# Dogfish3D_-_MCU_-_ATSAMD21G18_R1a.net
KiCad netlist of a schematic drawn in Altium Designer
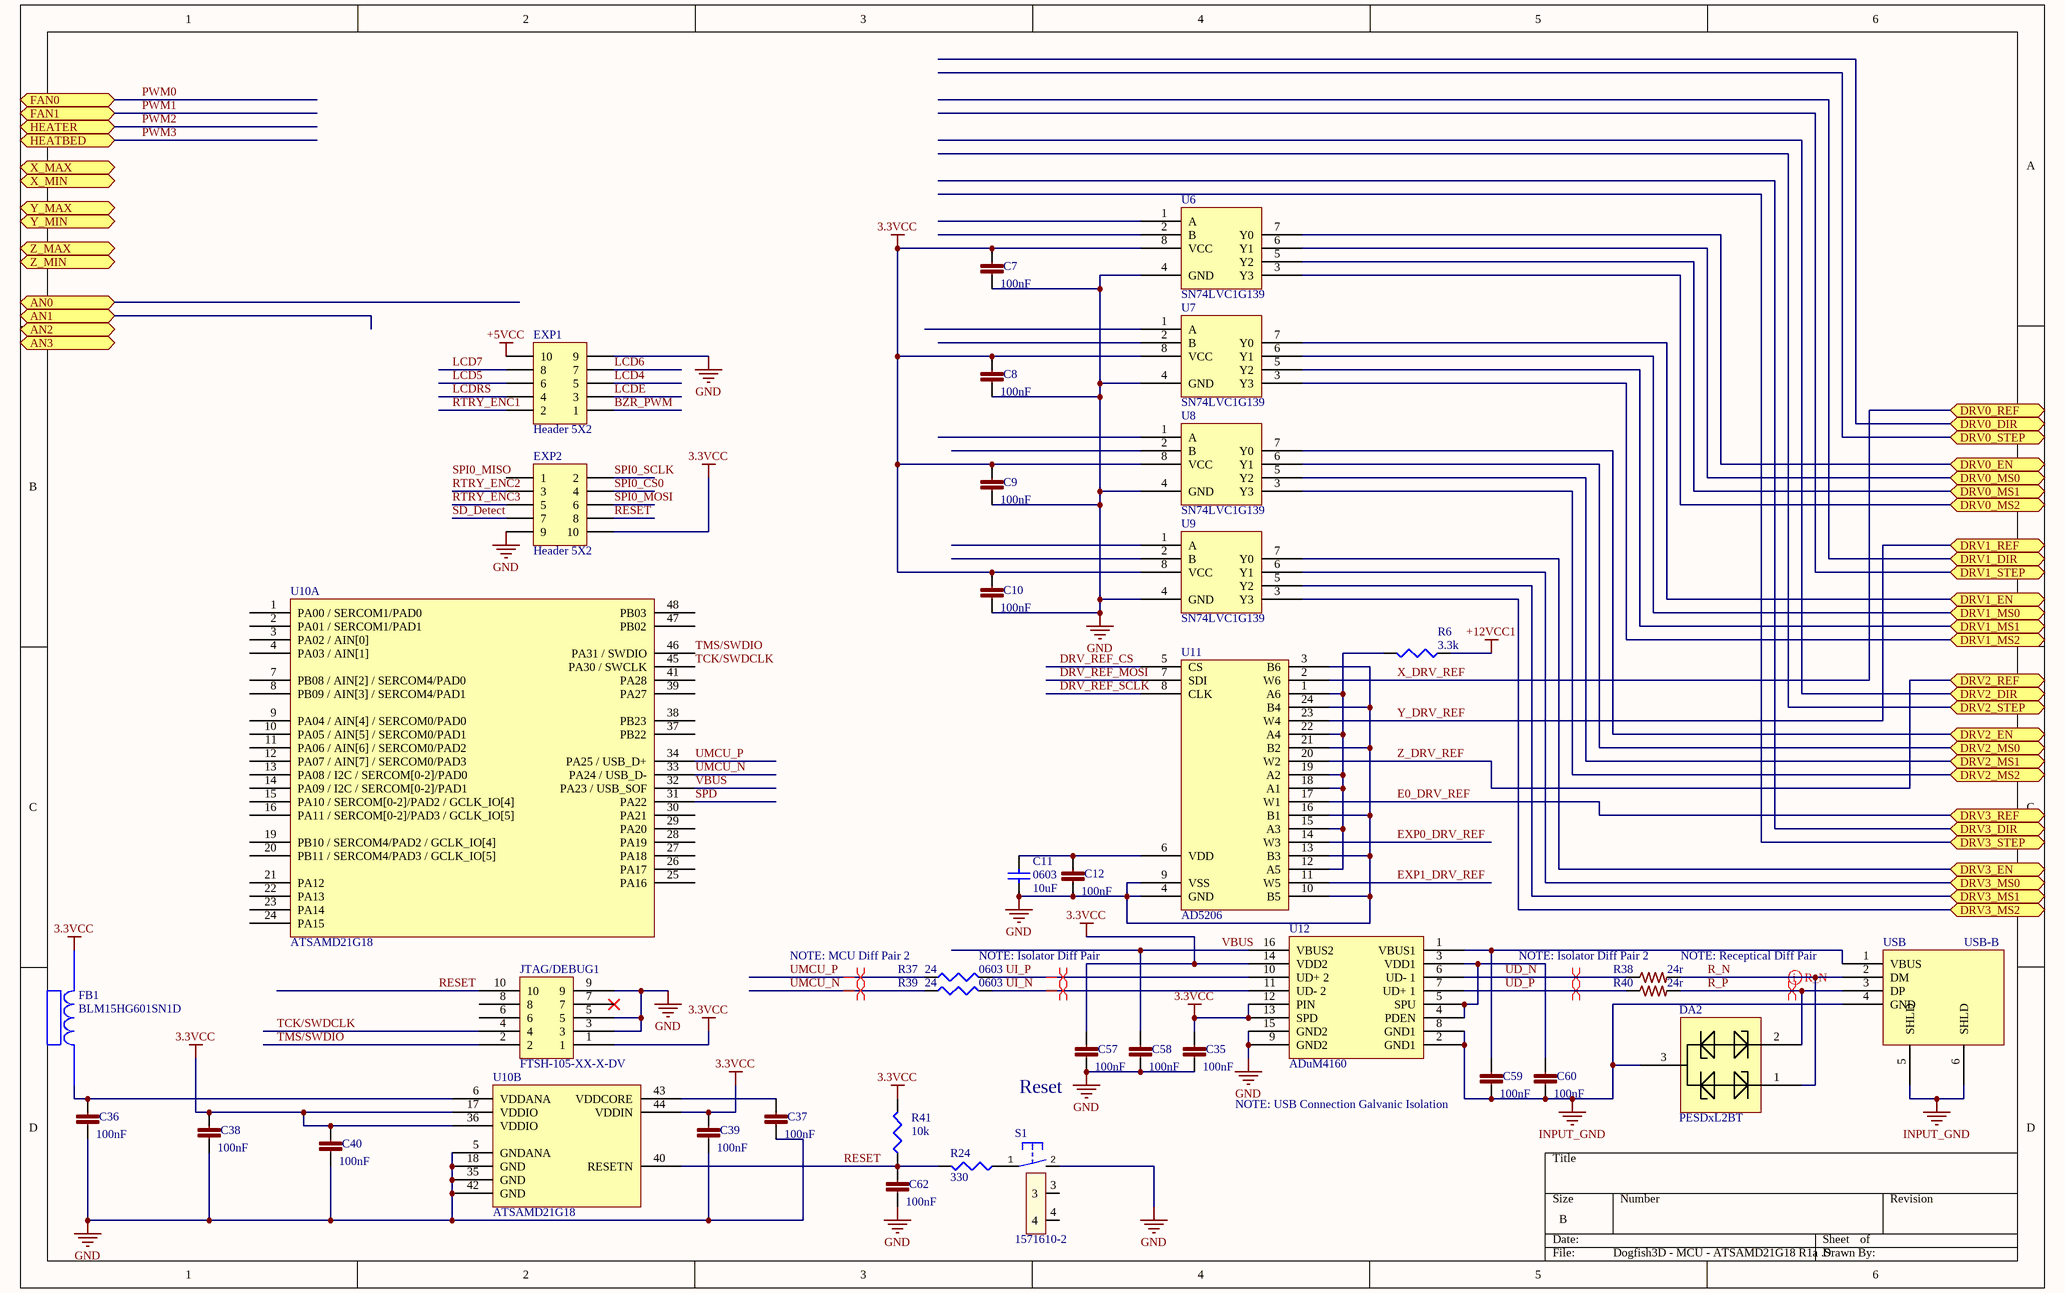
[diagram p0: Dogfish3D - MCU - ATSAMD21G18 R1a .SchDoc]

(export (version "E")
  (design (tool "Eeschema 10.0.6"))
  (components
    (comp (ref "C7")
      (value "100nF")
      (footprint "C0402")
      (description "CAP CER 0402 100nF 16V 10% X7R")
      (fields
        (field (name "MANUFACTURERPARTNUMBER") "GRM155R71C104KA88D")
        (field (name "PUBLISHER") "UltiMachine")
      )
      (libsource (lib "3Delight") (part "GRM155R71C104KA88D"))
    )
    (comp (ref "C8")
      (value "100nF")
      (footprint "C0402")
      (description "CAP CER 0402 100nF 16V 10% X7R")
      (fields
        (field (name "MANUFACTURERPARTNUMBER") "GRM155R71C104KA88D")
        (field (name "PUBLISHER") "UltiMachine")
      )
      (libsource (lib "3Delight") (part "GRM155R71C104KA88D"))
    )
    (comp (ref "C9")
      (value "100nF")
      (footprint "C0402")
      (description "CAP CER 0402 100nF 16V 10% X7R")
      (fields
        (field (name "MANUFACTURERPARTNUMBER") "GRM155R71C104KA88D")
        (field (name "PUBLISHER") "UltiMachine")
      )
      (libsource (lib "3Delight") (part "GRM155R71C104KA88D"))
    )
    (comp (ref "C10")
      (value "100nF")
      (footprint "C0402")
      (description "CAP CER 0402 100nF 16V 10% X7R")
      (fields
        (field (name "MANUFACTURERPARTNUMBER") "GRM155R71C104KA88D")
        (field (name "PUBLISHER") "UltiMachine")
      )
      (libsource (lib "3Delight") (part "GRM155R71C104KA88D"))
    )
    (comp (ref "C11")
      (value "0603")
      (footprint "1608[0603]")
      (description "Capacitor (Semiconductor SIM Model)")
      (fields (field (name "ALTIUM_VALUE") "10uF") (field (name "PUBLISHER") "Altium Limited"))
      (libsource (lib "Miscellaneous Devices") (part "Cap Semi"))
    )
    (comp (ref "C12")
      (value "100nF")
      (footprint "C0402")
      (description "CAP CER 0402 100nF 16V 10% X7R")
      (fields
        (field (name "MANUFACTURERPARTNUMBER") "GRM155R71C104KA88D")
        (field (name "PUBLISHER") "UltiMachine")
      )
      (libsource (lib "3Delight") (part "GRM155R71C104KA88D"))
    )
    (comp (ref "C35")
      (value "100nF")
      (footprint "C0402")
      (description "CAP CER 0402 100nF 16V 10% X7R")
      (fields
        (field (name "MANUFACTURERPARTNUMBER") "GRM155R71C104KA88D")
        (field (name "PUBLISHER") "UltiMachine")
      )
      (libsource (lib "3Delight") (part "GRM155R71C104KA88D"))
    )
    (comp (ref "C36")
      (value "100nF")
      (footprint "C0402")
      (description "CAP CER 0402 100nF 16V 10% X7R")
      (fields
        (field (name "MANUFACTURERPARTNUMBER") "GRM155R71C104KA88D")
        (field (name "PUBLISHER") "UltiMachine")
      )
      (libsource (lib "3Delight") (part "GRM155R71C104KA88D"))
    )
    (comp (ref "C37")
      (value "100nF")
      (footprint "C0402")
      (description "CAP CER 0402 100nF 16V 10% X7R")
      (fields
        (field (name "MANUFACTURERPARTNUMBER") "GRM155R71C104KA88D")
        (field (name "PUBLISHER") "UltiMachine")
      )
      (libsource (lib "3Delight") (part "GRM155R71C104KA88D"))
    )
    (comp (ref "C38")
      (value "100nF")
      (footprint "C0402")
      (description "CAP CER 0402 100nF 16V 10% X7R")
      (fields
        (field (name "MANUFACTURERPARTNUMBER") "GRM155R71C104KA88D")
        (field (name "PUBLISHER") "UltiMachine")
      )
      (libsource (lib "3Delight") (part "GRM155R71C104KA88D"))
    )
    (comp (ref "C39")
      (value "100nF")
      (footprint "C0402")
      (description "CAP CER 0402 100nF 16V 10% X7R")
      (fields
        (field (name "MANUFACTURERPARTNUMBER") "GRM155R71C104KA88D")
        (field (name "PUBLISHER") "UltiMachine")
      )
      (libsource (lib "3Delight") (part "GRM155R71C104KA88D"))
    )
    (comp (ref "C40")
      (value "100nF")
      (footprint "C0402")
      (description "CAP CER 0402 100nF 16V 10% X7R")
      (fields
        (field (name "MANUFACTURERPARTNUMBER") "GRM155R71C104KA88D")
        (field (name "PUBLISHER") "UltiMachine")
      )
      (libsource (lib "3Delight") (part "GRM155R71C104KA88D"))
    )
    (comp (ref "C57")
      (value "100nF")
      (footprint "C0402")
      (description "CAP CER 0402 100nF 16V 10% X7R")
      (fields
        (field (name "MANUFACTURERPARTNUMBER") "GRM155R71C104KA88D")
        (field (name "PUBLISHER") "UltiMachine")
      )
      (libsource (lib "3Delight") (part "GRM155R71C104KA88D"))
    )
    (comp (ref "C58")
      (value "100nF")
      (footprint "C0402")
      (description "CAP CER 0402 100nF 16V 10% X7R")
      (fields
        (field (name "MANUFACTURERPARTNUMBER") "GRM155R71C104KA88D")
        (field (name "PUBLISHER") "UltiMachine")
      )
      (libsource (lib "3Delight") (part "GRM155R71C104KA88D"))
    )
    (comp (ref "C59")
      (value "100nF")
      (footprint "C0402")
      (description "CAP CER 0402 100nF 16V 10% X7R")
      (fields
        (field (name "MANUFACTURERPARTNUMBER") "GRM155R71C104KA88D")
        (field (name "PUBLISHER") "UltiMachine")
      )
      (libsource (lib "3Delight") (part "GRM155R71C104KA88D"))
    )
    (comp (ref "C60")
      (value "100nF")
      (footprint "C0402")
      (description "CAP CER 0402 100nF 16V 10% X7R")
      (fields
        (field (name "MANUFACTURERPARTNUMBER") "GRM155R71C104KA88D")
        (field (name "PUBLISHER") "UltiMachine")
      )
      (libsource (lib "3Delight") (part "GRM155R71C104KA88D"))
    )
    (comp (ref "C62")
      (value "100nF")
      (footprint "C0402")
      (description "CAP CER 0402 100nF 16V 10% X7R")
      (fields
        (field (name "MANUFACTURERPARTNUMBER") "GRM155R71C104KA88D")
        (field (name "PUBLISHER") "UltiMachine")
      )
      (libsource (lib "3Delight") (part "GRM155R71C104KA88D"))
    )
    (comp (ref "DA2")
      (value "PESDxL2BT")
      (footprint "SOT95P230X110-3N")
      (description "PESDxL2BT TVS Diode Array 2x")
      (libsource (lib "ZMBo Schematic Library") (part "PESDxL2BT"))
    )
    (comp (ref "EXP1")
      (value "Header 5X2")
      (footprint "HDR2X5")
      (description "Header, 5-Pin, Dual row")
      (fields (field (name "PUBLISHER") "Altium Limited"))
      (libsource (lib "") (part "Header 5X2_1"))
    )
    (comp (ref "EXP2")
      (value "Header 5X2")
      (footprint "HDR2X5")
      (description "Header, 5-Pin, Dual row")
      (fields (field (name "PUBLISHER") "Altium Limited"))
      (libsource (lib "Miscellaneous Connectors") (part "Header 5X2"))
    )
    (comp (ref "FB1")
      (value "BLM15HG601SN1D")
      (footprint "BLM18PG121SN1D")
      (libsource (lib "AHD Part Library") (part "BLM15HG601SN1D"))
    )
    (comp (ref "JTAG/DEBUG1")
      (value "FTSH-105-XX-X-DV")
      (footprint "FTSH-105-XX-X-DV")
      (libsource (lib "Adams Altium Library") (part "ARM Cortex JTAG-DEBUG Header"))
    )
    (comp (ref "R6")
      (value "3.3k")
      (footprint "J1-0603")
      (description "Resistor")
      (fields (field (name "Comment") "Res3") (field (name "PUBLISHER") "Altium Limited"))
      (libsource (lib "Miscellaneous Devices") (part "Res3"))
    )
    (comp (ref "R24")
      (value "330")
      (footprint "J1-0603")
      (description "Resistor")
      (fields (field (name "Comment") "Res3") (field (name "PUBLISHER") "Altium Limited"))
      (libsource (lib "Miscellaneous Devices") (part "Res3"))
    )
    (comp (ref "R37")
      (value "0603")
      (footprint "J1-0603")
      (description "Resistor")
      (fields (field (name "ALTIUM_VALUE") "24") (field (name "PUBLISHER") "Altium Limited"))
      (libsource (lib "Miscellaneous Devices") (part "Res3"))
    )
    (comp (ref "R38")
      (value "24r")
      (footprint "R0603")
      (description "RES SMD 24 OHM 1% 1/10W 0603")
      (fields
        (field (name "MANUFACTURER") "Samsung")
        (field (name "MANUFACTURERPARTNUMBER") "RC0603FR-07100KL")
        (field (name "PUBLISHER") "UltiMachine")
      )
      (libsource (lib "Tigershark3D") (part "RC1608F240CS"))
    )
    (comp (ref "R39")
      (value "0603")
      (footprint "J1-0603")
      (description "Resistor")
      (fields (field (name "ALTIUM_VALUE") "24") (field (name "PUBLISHER") "Altium Limited"))
      (libsource (lib "Miscellaneous Devices") (part "Res3"))
    )
    (comp (ref "R40")
      (value "24r")
      (footprint "R0603")
      (description "RES SMD 24 OHM 1% 1/10W 0603")
      (fields
        (field (name "MANUFACTURER") "Samsung")
        (field (name "MANUFACTURERPARTNUMBER") "RC0603FR-07100KL")
        (field (name "PUBLISHER") "UltiMachine")
      )
      (libsource (lib "Tigershark3D") (part "RC1608F240CS"))
    )
    (comp (ref "R41")
      (value "10k")
      (footprint "J1-0603")
      (description "Resistor")
      (fields (field (name "Comment") "Res3") (field (name "PUBLISHER") "Altium Limited"))
      (libsource (lib "Miscellaneous Devices") (part "Res3"))
    )
    (comp (ref "S1")
      (value "1571610-2")
      (footprint "B3F-31XX")
      (description "SWTCH Momentary Washable")
      (fields
        (field (name "MANUFACTURER") "Omron")
        (field (name "MANUFACTURER_1") "TE")
        (field (name "PUBLISHER") "UltiMachine")
      )
      (libsource (lib "ZMBo Schematic Library") (part "1571610-2_1"))
    )
    (comp (ref "U6")
      (value "SN74LVC1G139")
      (footprint "Ti DCU (R-PDSO-G8) SOIC - SN74VC1G139")
      (libsource (lib "Dogfish3D") (part "SN74LVC1G139"))
    )
    (comp (ref "U7")
      (value "SN74LVC1G139")
      (footprint "Ti DCU (R-PDSO-G8) SOIC - SN74VC1G139")
      (libsource (lib "Dogfish3D") (part "SN74LVC1G139"))
    )
    (comp (ref "U8")
      (value "SN74LVC1G139")
      (footprint "Ti DCU (R-PDSO-G8) SOIC - SN74VC1G139")
      (libsource (lib "Dogfish3D") (part "SN74LVC1G139"))
    )
    (comp (ref "U9")
      (value "SN74LVC1G139")
      (footprint "Ti DCU (R-PDSO-G8) SOIC - SN74VC1G139")
      (libsource (lib "Dogfish3D") (part "SN74LVC1G139"))
    )
    (comp (ref "U10")
      (value "ATSAMD21G18")
      (footprint "TSQFP50P900X900X120-48N")
      (libsource (lib "Dogfish3D") (part "ATSAMD21G18"))
    )
    (comp (ref "U11")
      (value "AD5206")
      (footprint "AD5206 & AD5204")
      (libsource (lib "ZMBo Schematic Library") (part "AD5206"))
    )
    (comp (ref "U12")
      (value "ADuM4160")
      (footprint "ADuM4160")
      (description "USB Opto Isolator")
      (libsource (lib "ZMBo Schematic Library") (part "ADuM4160"))
    )
    (comp (ref "USB")
      (value "USB-B")
      (footprint "PN61729")
      (libsource (lib "ZMBo Schematic Library") (part "USB-B"))
    )
  )
  (nets
    (net (code "1") (name "+5VCC") (class "Default")
      (node (ref "EXP1") (pin "10") (pinfunction "10_10") (pintype "passive"))
    )
    (net (code "2") (name "+12VCC1") (class "Default")
      (node (ref "R6") (pin "1") (pinfunction "1_1") (pintype "passive"))
    )
    (net (code "7") (name "/BZR_PWM") (class "Default")
      (node (ref "EXP1") (pin "1") (pinfunction "1_1") (pintype "passive"))
    )
    (net (code "9") (name "/DRV0_EN") (class "Default")
      (node (ref "U6") (pin "7") (pinfunction "Y0_7") (pintype "passive"))
    )
    (net (code "10") (name "/DRV0_MS0") (class "Default")
      (node (ref "U6") (pin "6") (pinfunction "Y1_6") (pintype "passive"))
    )
    (net (code "11") (name "/DRV0_MS1") (class "Default")
      (node (ref "U6") (pin "5") (pinfunction "Y2_5") (pintype "passive"))
    )
    (net (code "12") (name "/DRV0_MS2") (class "Default")
      (node (ref "U6") (pin "3") (pinfunction "Y3_3") (pintype "passive"))
    )
    (net (code "15") (name "/DRV1_EN") (class "Default")
      (node (ref "U7") (pin "7") (pinfunction "Y0_7") (pintype "passive"))
    )
    (net (code "16") (name "/DRV1_MS0") (class "Default")
      (node (ref "U7") (pin "6") (pinfunction "Y1_6") (pintype "passive"))
    )
    (net (code "17") (name "/DRV1_MS1") (class "Default")
      (node (ref "U7") (pin "5") (pinfunction "Y2_5") (pintype "passive"))
    )
    (net (code "18") (name "/DRV1_MS2") (class "Default")
      (node (ref "U7") (pin "3") (pinfunction "Y3_3") (pintype "passive"))
    )
    (net (code "21") (name "/DRV2_EN") (class "Default")
      (node (ref "U8") (pin "7") (pinfunction "Y0_7") (pintype "passive"))
    )
    (net (code "22") (name "/DRV2_MS0") (class "Default")
      (node (ref "U8") (pin "6") (pinfunction "Y1_6") (pintype "passive"))
    )
    (net (code "23") (name "/DRV2_MS1") (class "Default")
      (node (ref "U8") (pin "5") (pinfunction "Y2_5") (pintype "passive"))
    )
    (net (code "24") (name "/DRV2_MS2") (class "Default")
      (node (ref "U8") (pin "3") (pinfunction "Y3_3") (pintype "passive"))
    )
    (net (code "27") (name "/DRV3_EN") (class "Default")
      (node (ref "U9") (pin "7") (pinfunction "Y0_7") (pintype "passive"))
    )
    (net (code "28") (name "/DRV3_MS0") (class "Default")
      (node (ref "U9") (pin "6") (pinfunction "Y1_6") (pintype "passive"))
    )
    (net (code "29") (name "/DRV3_MS1") (class "Default")
      (node (ref "U9") (pin "5") (pinfunction "Y2_5") (pintype "passive"))
    )
    (net (code "30") (name "/DRV3_MS2") (class "Default")
      (node (ref "U9") (pin "3") (pinfunction "Y3_3") (pintype "passive"))
    )
    (net (code "32") (name "/DRV_REF_CS") (class "Default")
      (node (ref "U11") (pin "5") (pinfunction "CS_5") (pintype "passive"))
    )
    (net (code "33") (name "/DRV_REF_MOSI") (class "Default")
      (node (ref "U11") (pin "7") (pinfunction "SDI_7") (pintype "passive"))
    )
    (net (code "34") (name "/DRV_REF_SCLK") (class "Default")
      (node (ref "U11") (pin "8") (pinfunction "CLK_8") (pintype "passive"))
    )
    (net (code "35") (name "/E0_DRV_REF") (class "Default")
      (node (ref "U11") (pin "17") (pinfunction "W1_17") (pintype "passive"))
    )
    (net (code "36") (name "/EXP0_DRV_REF") (class "Default")
      (node (ref "U11") (pin "14") (pinfunction "W3_14") (pintype "passive"))
    )
    (net (code "37") (name "/EXP1_DRV_REF") (class "Default")
      (node (ref "U11") (pin "11") (pinfunction "W5_11") (pintype "passive"))
    )
    (net (code "38") (name "/LCD4") (class "Default")
      (node (ref "EXP1") (pin "5") (pinfunction "5_5") (pintype "passive"))
    )
    (net (code "39") (name "/LCD5") (class "Default")
      (node (ref "EXP1") (pin "6") (pinfunction "6_6") (pintype "passive"))
    )
    (net (code "40") (name "/LCD6") (class "Default")
      (node (ref "EXP1") (pin "7") (pinfunction "7_7") (pintype "passive"))
    )
    (net (code "41") (name "/LCD7") (class "Default")
      (node (ref "EXP1") (pin "8") (pinfunction "8_8") (pintype "passive"))
    )
    (net (code "42") (name "/LCDE") (class "Default")
      (node (ref "EXP1") (pin "3") (pinfunction "3_3") (pintype "passive"))
    )
    (net (code "43") (name "/LCDRS") (class "Default")
      (node (ref "EXP1") (pin "4") (pinfunction "4_4") (pintype "passive"))
    )
    (net (code "48") (name "/RESET") (class "Default")
      (node (ref "C62") (pin "1") (pinfunction "1_1") (pintype "passive"))
      (node (ref "EXP2") (pin "8") (pinfunction "8_8") (pintype "passive"))
      (node (ref "JTAG/DEBUG1") (pin "10") (pinfunction "10_10") (pintype "passive"))
      (node (ref "R24") (pin "2") (pinfunction "2_2") (pintype "passive"))
      (node (ref "R41") (pin "1") (pinfunction "1_1") (pintype "passive"))
      (node (ref "U10") (pin "40") (pinfunction "RESETN_40") (pintype "passive"))
    )
    (net (code "49") (name "/RTRY_ENC1") (class "Default")
      (node (ref "EXP1") (pin "2") (pinfunction "2_2") (pintype "passive"))
    )
    (net (code "50") (name "/RTRY_ENC2") (class "Default")
      (node (ref "EXP2") (pin "3") (pinfunction "3_3") (pintype "passive"))
    )
    (net (code "51") (name "/RTRY_ENC3") (class "Default")
      (node (ref "EXP2") (pin "5") (pinfunction "5_5") (pintype "passive"))
    )
    (net (code "52") (name "/R_N") (class "Default")
      (node (ref "DA2") (pin "1") (pinfunction "1_1") (pintype "passive"))
      (node (ref "R38") (pin "2") (pinfunction "2_2") (pintype "passive"))
      (node (ref "USB") (pin "2") (pinfunction "DM_2") (pintype "passive"))
    )
    (net (code "53") (name "/R_P") (class "Default")
      (node (ref "DA2") (pin "2") (pinfunction "2_2") (pintype "passive"))
      (node (ref "R40") (pin "2") (pinfunction "2_2") (pintype "passive"))
      (node (ref "USB") (pin "3") (pinfunction "DP_3") (pintype "passive"))
    )
    (net (code "54") (name "/SD_Detect") (class "Default")
      (node (ref "EXP2") (pin "7") (pinfunction "7_7") (pintype "passive"))
    )
    (net (code "55") (name "/SPD") (class "Default")
      (node (ref "U10") (pin "31") (pinfunction "PA22_31") (pintype "passive"))
    )
    (net (code "56") (name "/SPI0_CS0") (class "Default")
      (node (ref "EXP2") (pin "4") (pinfunction "4_4") (pintype "passive"))
    )
    (net (code "58") (name "/SPI0_MOSI") (class "Default")
      (node (ref "EXP2") (pin "6") (pinfunction "6_6") (pintype "passive"))
    )
    (net (code "59") (name "/SPI0_SCLK") (class "Default")
      (node (ref "EXP2") (pin "2") (pinfunction "2_2") (pintype "passive"))
    )
    (net (code "60") (name "/TCK{slash}SWDCLK") (class "Default")
      (node (ref "JTAG/DEBUG1") (pin "4") (pinfunction "4_4") (pintype "passive"))
      (node (ref "U10") (pin "45") (pinfunction "PA30_/_SWCLK_45") (pintype "passive"))
    )
    (net (code "61") (name "/TMS{slash}SWDIO") (class "Default")
      (node (ref "JTAG/DEBUG1") (pin "2") (pinfunction "2_2") (pintype "passive"))
      (node (ref "U10") (pin "46") (pinfunction "PA31_/_SWDIO_46") (pintype "passive"))
    )
    (net (code "62") (name "/UD_N") (class "Default")
      (node (ref "R38") (pin "1") (pinfunction "1_1") (pintype "passive"))
      (node (ref "U12") (pin "6") (pinfunction "UD-_1_6") (pintype "passive"))
    )
    (net (code "63") (name "/UD_P") (class "Default")
      (node (ref "R40") (pin "1") (pinfunction "1_1") (pintype "passive"))
      (node (ref "U12") (pin "7") (pinfunction "UD+_1_7") (pintype "passive"))
    )
    (net (code "64") (name "/UI_N") (class "Default")
      (node (ref "R39") (pin "2") (pinfunction "2_2") (pintype "passive"))
      (node (ref "U12") (pin "11") (pinfunction "UD-_2_11") (pintype "passive"))
    )
    (net (code "65") (name "/UI_P") (class "Default")
      (node (ref "R37") (pin "2") (pinfunction "2_2") (pintype "passive"))
      (node (ref "U12") (pin "10") (pinfunction "UD+_2_10") (pintype "passive"))
    )
    (net (code "66") (name "/UMCU_N") (class "Default")
      (node (ref "R39") (pin "1") (pinfunction "1_1") (pintype "passive"))
      (node (ref "U10") (pin "33") (pinfunction "PA24_/_USB_D-_33") (pintype "passive"))
    )
    (net (code "67") (name "/UMCU_P") (class "Default")
      (node (ref "R37") (pin "1") (pinfunction "1_1") (pintype "passive"))
      (node (ref "U10") (pin "34") (pinfunction "PA25_/_USB_D+_34") (pintype "passive"))
    )
    (net (code "68") (name "/VBUS") (class "Default")
      (node (ref "C58") (pin "1") (pinfunction "1_1") (pintype "passive"))
      (node (ref "U10") (pin "32") (pinfunction "PA23_/_USB_SOF_32") (pintype "passive"))
      (node (ref "U12") (pin "16") (pinfunction "VBUS2_16") (pintype "passive"))
    )
    (net (code "69") (name "/X_DRV_REF") (class "Default")
      (node (ref "U11") (pin "2") (pinfunction "W6_2") (pintype "passive"))
    )
    (net (code "72") (name "/Y_DRV_REF") (class "Default")
      (node (ref "U11") (pin "23") (pinfunction "W4_23") (pintype "passive"))
    )
    (net (code "75") (name "/Z_DRV_REF") (class "Default")
      (node (ref "U11") (pin "20") (pinfunction "W2_20") (pintype "passive"))
    )
    (net (code "78") (name "3.3VCC") (class "Default")
      (node (ref "C10") (pin "1") (pinfunction "1_1") (pintype "passive"))
      (node (ref "C35") (pin "1") (pinfunction "1_1") (pintype "passive"))
      (node (ref "C38") (pin "1") (pinfunction "1_1") (pintype "passive"))
      (node (ref "C39") (pin "1") (pinfunction "1_1") (pintype "passive"))
      (node (ref "C40") (pin "1") (pinfunction "1_1") (pintype "passive"))
      (node (ref "C57") (pin "1") (pinfunction "1_1") (pintype "passive"))
      (node (ref "C7") (pin "1") (pinfunction "1_1") (pintype "passive"))
      (node (ref "C8") (pin "1") (pinfunction "1_1") (pintype "passive"))
      (node (ref "C9") (pin "1") (pinfunction "1_1") (pintype "passive"))
      (node (ref "EXP2") (pin "10") (pinfunction "10_10") (pintype "passive"))
      (node (ref "FB1") (pin "2") (pinfunction "2_2") (pintype "passive"))
      (node (ref "JTAG/DEBUG1") (pin "1") (pinfunction "1_1") (pintype "passive"))
      (node (ref "R41") (pin "2") (pinfunction "2_2") (pintype "passive"))
      (node (ref "U10") (pin "17") (pinfunction "VDDIO_17") (pintype "passive"))
      (node (ref "U10") (pin "36") (pinfunction "VDDIO_36") (pintype "passive"))
      (node (ref "U10") (pin "44") (pinfunction "VDDIN_44") (pintype "passive"))
      (node (ref "U12") (pin "12") (pinfunction "PIN_12") (pintype "passive"))
      (node (ref "U12") (pin "13") (pinfunction "SPD_13") (pintype "passive"))
      (node (ref "U12") (pin "14") (pinfunction "VDD2_14") (pintype "passive"))
      (node (ref "U6") (pin "8") (pinfunction "VCC_8") (pintype "passive"))
      (node (ref "U7") (pin "8") (pinfunction "VCC_8") (pintype "passive"))
      (node (ref "U8") (pin "8") (pinfunction "VCC_8") (pintype "passive"))
      (node (ref "U9") (pin "8") (pinfunction "VCC_8") (pintype "passive"))
    )
    (net (code "79") (name "GND") (class "Default")
      (node (ref "C10") (pin "2") (pinfunction "2_2") (pintype "passive"))
      (node (ref "C11") (pin "1") (pinfunction "1_1") (pintype "passive"))
      (node (ref "C12") (pin "2") (pinfunction "2_2") (pintype "passive"))
      (node (ref "C35") (pin "2") (pinfunction "2_2") (pintype "passive"))
      (node (ref "C36") (pin "2") (pinfunction "2_2") (pintype "passive"))
      (node (ref "C37") (pin "2") (pinfunction "2_2") (pintype "passive"))
      (node (ref "C38") (pin "2") (pinfunction "2_2") (pintype "passive"))
      (node (ref "C39") (pin "2") (pinfunction "2_2") (pintype "passive"))
      (node (ref "C40") (pin "2") (pinfunction "2_2") (pintype "passive"))
      (node (ref "C57") (pin "2") (pinfunction "2_2") (pintype "passive"))
      (node (ref "C58") (pin "2") (pinfunction "2_2") (pintype "passive"))
      (node (ref "C62") (pin "2") (pinfunction "2_2") (pintype "passive"))
      (node (ref "C7") (pin "2") (pinfunction "2_2") (pintype "passive"))
      (node (ref "C8") (pin "2") (pinfunction "2_2") (pintype "passive"))
      (node (ref "C9") (pin "2") (pinfunction "2_2") (pintype "passive"))
      (node (ref "EXP1") (pin "9") (pinfunction "9_9") (pintype "passive"))
      (node (ref "EXP2") (pin "9") (pinfunction "9_9") (pintype "passive"))
      (node (ref "JTAG/DEBUG1") (pin "3") (pinfunction "3_3") (pintype "passive"))
      (node (ref "JTAG/DEBUG1") (pin "5") (pinfunction "5_5") (pintype "passive"))
      (node (ref "JTAG/DEBUG1") (pin "9") (pinfunction "9_9") (pintype "passive"))
      (node (ref "S1") (pin "2") (pinfunction "S_2") (pintype "passive"))
      (node (ref "U10") (pin "18") (pinfunction "GND_18") (pintype "passive"))
      (node (ref "U10") (pin "35") (pinfunction "GND_35") (pintype "passive"))
      (node (ref "U10") (pin "42") (pinfunction "GND_42") (pintype "passive"))
      (node (ref "U10") (pin "5") (pinfunction "GNDANA_5") (pintype "passive"))
      (node (ref "U11") (pin "10") (pinfunction "B5_10") (pintype "passive"))
      (node (ref "U11") (pin "13") (pinfunction "B3_13") (pintype "passive"))
      (node (ref "U11") (pin "16") (pinfunction "B1_16") (pintype "passive"))
      (node (ref "U11") (pin "21") (pinfunction "B2_21") (pintype "passive"))
      (node (ref "U11") (pin "24") (pinfunction "B4_24") (pintype "passive"))
      (node (ref "U11") (pin "3") (pinfunction "B6_3") (pintype "passive"))
      (node (ref "U11") (pin "4") (pinfunction "GND_4") (pintype "passive"))
      (node (ref "U11") (pin "9") (pinfunction "VSS_9") (pintype "passive"))
      (node (ref "U12") (pin "15") (pinfunction "GND2_15") (pintype "passive"))
      (node (ref "U12") (pin "9") (pinfunction "GND2_9") (pintype "passive"))
      (node (ref "U6") (pin "4") (pinfunction "GND_4") (pintype "passive"))
      (node (ref "U7") (pin "4") (pinfunction "GND_4") (pintype "passive"))
      (node (ref "U8") (pin "4") (pinfunction "GND_4") (pintype "passive"))
      (node (ref "U9") (pin "4") (pinfunction "GND_4") (pintype "passive"))
    )
    (net (code "80") (name "INPUT_GND") (class "Default")
      (node (ref "C59") (pin "2") (pinfunction "2_2") (pintype "passive"))
      (node (ref "C60") (pin "2") (pinfunction "2_2") (pintype "passive"))
      (node (ref "DA2") (pin "3") (pinfunction "3_3") (pintype "passive"))
      (node (ref "U12") (pin "2") (pinfunction "GND1_2") (pintype "passive"))
      (node (ref "U12") (pin "8") (pinfunction "GND1_8") (pintype "passive"))
      (node (ref "USB") (pin "4") (pinfunction "GND_4") (pintype "passive"))
      (node (ref "USB") (pin "5") (pinfunction "SHLD_5") (pintype "passive"))
      (node (ref "USB") (pin "6") (pinfunction "SHLD_6") (pintype "passive"))
    )
    (net (code "81") (name "Net-(S1-P)") (class "Default")
      (node (ref "R24") (pin "1") (pinfunction "1_1") (pintype "passive"))
      (node (ref "S1") (pin "1") (pinfunction "P_1") (pintype "passive"))
    )
    (net (code "82") (name "Net-(U10B-VDDANA)") (class "Default")
      (node (ref "C36") (pin "1") (pinfunction "1_1") (pintype "passive"))
      (node (ref "FB1") (pin "1") (pinfunction "1_1") (pintype "passive"))
      (node (ref "U10") (pin "6") (pinfunction "VDDANA_6") (pintype "passive"))
    )
    (net (code "83") (name "Net-(U10B-VDDCORE)") (class "Default")
      (node (ref "C37") (pin "1") (pinfunction "1_1") (pintype "passive"))
      (node (ref "U10") (pin "43") (pinfunction "VDDCORE_43") (pintype "passive"))
    )
    (net (code "84") (name "Net-(U11-A1)") (class "Default")
      (node (ref "R6") (pin "2") (pinfunction "2_2") (pintype "passive"))
      (node (ref "U11") (pin "1") (pinfunction "A6_1") (pintype "passive"))
      (node (ref "U11") (pin "12") (pinfunction "A5_12") (pintype "passive"))
      (node (ref "U11") (pin "15") (pinfunction "A3_15") (pintype "passive"))
      (node (ref "U11") (pin "18") (pinfunction "A1_18") (pintype "passive"))
      (node (ref "U11") (pin "19") (pinfunction "A2_19") (pintype "passive"))
      (node (ref "U11") (pin "22") (pinfunction "A4_22") (pintype "passive"))
    )
    (net (code "85") (name "Net-(U11-VDD)") (class "Default")
      (node (ref "C11") (pin "2") (pinfunction "2_2") (pintype "passive"))
      (node (ref "C12") (pin "1") (pinfunction "1_1") (pintype "passive"))
      (node (ref "U11") (pin "6") (pinfunction "VDD_6") (pintype "passive"))
    )
    (net (code "86") (name "Net-(U12-PDEN)") (class "Default")
      (node (ref "C60") (pin "1") (pinfunction "1_1") (pintype "passive"))
      (node (ref "U12") (pin "3") (pinfunction "VDD1_3") (pintype "passive"))
      (node (ref "U12") (pin "4") (pinfunction "PDEN_4") (pintype "passive"))
      (node (ref "U12") (pin "5") (pinfunction "SPU_5") (pintype "passive"))
    )
    (net (code "87") (name "Net-(U12-VBUS1)") (class "Default")
      (node (ref "C59") (pin "1") (pinfunction "1_1") (pintype "passive"))
      (node (ref "U12") (pin "1") (pinfunction "VBUS1_1") (pintype "passive"))
      (node (ref "USB") (pin "1") (pinfunction "VBUS_1") (pintype "passive"))
    )
    (net (code "88") (name "unconnected-(EXP2-Pad1)") (class "Default")
      (node (ref "EXP2") (pin "1") (pinfunction "1_1") (pintype "passive"))
    )
    (net (code "89") (name "unconnected-(JTAG/DEBUG1-Pad6)") (class "Default")
      (node (ref "JTAG/DEBUG1") (pin "6") (pinfunction "6_6") (pintype "passive"))
    )
    (net (code "90") (name "unconnected-(JTAG/DEBUG1-Pad7)") (class "Default")
      (node (ref "JTAG/DEBUG1") (pin "7") (pinfunction "7_7") (pintype "passive+no_connect"))
    )
    (net (code "91") (name "unconnected-(JTAG/DEBUG1-Pad8)") (class "Default")
      (node (ref "JTAG/DEBUG1") (pin "8") (pinfunction "8_8") (pintype "passive"))
    )
    (net (code "92") (name "unconnected-(S1-Pad3)") (class "Default")
      (node (ref "S1") (pin "3") (pinfunction "3_3") (pintype "power_in"))
    )
    (net (code "93") (name "unconnected-(S1-Pad4)") (class "Default")
      (node (ref "S1") (pin "4") (pinfunction "4_4") (pintype "power_in"))
    )
    (net (code "94") (name "unconnected-(U6-A-Pad1)") (class "Default")
      (node (ref "U6") (pin "1") (pinfunction "A_1") (pintype "passive"))
    )
    (net (code "95") (name "unconnected-(U6-B-Pad2)") (class "Default")
      (node (ref "U6") (pin "2") (pinfunction "B_2") (pintype "passive"))
    )
    (net (code "96") (name "unconnected-(U7-A-Pad1)") (class "Default")
      (node (ref "U7") (pin "1") (pinfunction "A_1") (pintype "passive"))
    )
    (net (code "97") (name "unconnected-(U7-B-Pad2)") (class "Default")
      (node (ref "U7") (pin "2") (pinfunction "B_2") (pintype "passive"))
    )
    (net (code "98") (name "unconnected-(U8-A-Pad1)") (class "Default")
      (node (ref "U8") (pin "1") (pinfunction "A_1") (pintype "passive"))
    )
    (net (code "99") (name "unconnected-(U8-B-Pad2)") (class "Default")
      (node (ref "U8") (pin "2") (pinfunction "B_2") (pintype "passive"))
    )
    (net (code "100") (name "unconnected-(U9-A-Pad1)") (class "Default")
      (node (ref "U9") (pin "1") (pinfunction "A_1") (pintype "passive"))
    )
    (net (code "101") (name "unconnected-(U9-B-Pad2)") (class "Default")
      (node (ref "U9") (pin "2") (pinfunction "B_2") (pintype "passive"))
    )
    (net (code "102") (name "unconnected-(U10A-PA00_{slash}_SERCOM1{slash}PAD0-Pad1)") (class "Default")
      (node (ref "U10") (pin "1") (pinfunction "PA00_/_SERCOM1/PAD0_1") (pintype "passive"))
    )
    (net (code "103") (name "unconnected-(U10A-PA01_{slash}_SERCOM1{slash}PAD1-Pad2)") (class "Default")
      (node (ref "U10") (pin "2") (pinfunction "PA01_/_SERCOM1/PAD1_2") (pintype "passive"))
    )
    (net (code "104") (name "unconnected-(U10A-PA02_{slash}_AIN[0]-Pad3)") (class "Default")
      (node (ref "U10") (pin "3") (pinfunction "PA02_/_AIN[0]_3") (pintype "passive"))
    )
    (net (code "105") (name "unconnected-(U10A-PA03_{slash}_AIN[1]-Pad4)") (class "Default")
      (node (ref "U10") (pin "4") (pinfunction "PA03_/_AIN[1]_4") (pintype "passive"))
    )
    (net (code "106") (name "unconnected-(U10A-PA04_{slash}_AIN[4]_{slash}_SERCOM0{slash}PAD0-Pad9)") (class "Default")
      (node (ref "U10") (pin "9") (pinfunction "PA04_/_AIN[4]_/_SERCOM0/PAD0_9") (pintype "passive"))
    )
    (net (code "107") (name "unconnected-(U10A-PA05_{slash}_AIN[5]_{slash}_SERCOM0{slash}PAD1-Pad10)") (class "Default")
      (node (ref "U10") (pin "10") (pinfunction "PA05_/_AIN[5]_/_SERCOM0/PAD1_10") (pintype "passive"))
    )
    (net (code "108") (name "unconnected-(U10A-PA06_{slash}_AIN[6]_{slash}_SERCOM0{slash}PAD2-Pad11)") (class "Default")
      (node (ref "U10") (pin "11") (pinfunction "PA06_/_AIN[6]_/_SERCOM0/PAD2_11") (pintype "passive"))
    )
    (net (code "109") (name "unconnected-(U10A-PA07_{slash}_AIN[7]_{slash}_SERCOM0{slash}PAD3-Pad12)") (class "Default")
      (node (ref "U10") (pin "12") (pinfunction "PA07_/_AIN[7]_/_SERCOM0/PAD3_12") (pintype "passive"))
    )
    (net (code "110") (name "unconnected-(U10A-PA08_{slash}_I2C_{slash}_SERCOM[0-2]{slash}PAD0-Pad13)") (class "Default")
      (node (ref "U10") (pin "13") (pinfunction "PA08_/_I2C_/_SERCOM[0-2]/PAD0_13") (pintype "passive"))
    )
    (net (code "111") (name "unconnected-(U10A-PA09_{slash}_I2C_{slash}_SERCOM[0-2]{slash}PAD1-Pad14)") (class "Default")
      (node (ref "U10") (pin "14") (pinfunction "PA09_/_I2C_/_SERCOM[0-2]/PAD1_14") (pintype "passive"))
    )
    (net (code "112") (name "unconnected-(U10A-PA10_{slash}_SERCOM[0-2]{slash}PAD2_{slash}_GCLK_IO[4]-Pad15)") (class "Default")
      (node (ref "U10") (pin "15") (pinfunction "PA10_/_SERCOM[0-2]/PAD2_/_GCLK_IO[4]_15") (pintype "passive"))
    )
    (net (code "113") (name "unconnected-(U10A-PA11_{slash}_SERCOM[0-2]{slash}PAD3_{slash}_GCLK_IO[5]-Pad16)") (class "Default")
      (node (ref "U10") (pin "16") (pinfunction "PA11_/_SERCOM[0-2]/PAD3_/_GCLK_IO[5]_16") (pintype "passive"))
    )
    (net (code "114") (name "unconnected-(U10A-PA12-Pad21)") (class "Default")
      (node (ref "U10") (pin "21") (pinfunction "PA12_21") (pintype "passive"))
    )
    (net (code "115") (name "unconnected-(U10A-PA13-Pad22)") (class "Default")
      (node (ref "U10") (pin "22") (pinfunction "PA13_22") (pintype "passive"))
    )
    (net (code "116") (name "unconnected-(U10A-PA14-Pad23)") (class "Default")
      (node (ref "U10") (pin "23") (pinfunction "PA14_23") (pintype "passive"))
    )
    (net (code "117") (name "unconnected-(U10A-PA15-Pad24)") (class "Default")
      (node (ref "U10") (pin "24") (pinfunction "PA15_24") (pintype "passive"))
    )
    (net (code "118") (name "unconnected-(U10A-PA16-Pad25)") (class "Default")
      (node (ref "U10") (pin "25") (pinfunction "PA16_25") (pintype "passive"))
    )
    (net (code "119") (name "unconnected-(U10A-PA17-Pad26)") (class "Default")
      (node (ref "U10") (pin "26") (pinfunction "PA17_26") (pintype "passive"))
    )
    (net (code "120") (name "unconnected-(U10A-PA18-Pad27)") (class "Default")
      (node (ref "U10") (pin "27") (pinfunction "PA18_27") (pintype "passive"))
    )
    (net (code "121") (name "unconnected-(U10A-PA19-Pad28)") (class "Default")
      (node (ref "U10") (pin "28") (pinfunction "PA19_28") (pintype "passive"))
    )
    (net (code "122") (name "unconnected-(U10A-PA20-Pad29)") (class "Default")
      (node (ref "U10") (pin "29") (pinfunction "PA20_29") (pintype "passive"))
    )
    (net (code "123") (name "unconnected-(U10A-PA21-Pad30)") (class "Default")
      (node (ref "U10") (pin "30") (pinfunction "PA21_30") (pintype "passive"))
    )
    (net (code "124") (name "unconnected-(U10A-PA27-Pad39)") (class "Default")
      (node (ref "U10") (pin "39") (pinfunction "PA27_39") (pintype "passive"))
    )
    (net (code "125") (name "unconnected-(U10A-PA28-Pad41)") (class "Default")
      (node (ref "U10") (pin "41") (pinfunction "PA28_41") (pintype "passive"))
    )
    (net (code "126") (name "unconnected-(U10A-PB02-Pad47)") (class "Default")
      (node (ref "U10") (pin "47") (pinfunction "PB02_47") (pintype "passive"))
    )
    (net (code "127") (name "unconnected-(U10A-PB03-Pad48)") (class "Default")
      (node (ref "U10") (pin "48") (pinfunction "PB03_48") (pintype "passive"))
    )
    (net (code "128") (name "unconnected-(U10A-PB08_{slash}_AIN[2]_{slash}_SERCOM4{slash}PAD0-Pad7)") (class "Default")
      (node (ref "U10") (pin "7") (pinfunction "PB08_/_AIN[2]_/_SERCOM4/PAD0_7") (pintype "passive"))
    )
    (net (code "129") (name "unconnected-(U10A-PB09_{slash}_AIN[3]_{slash}_SERCOM4{slash}PAD1-Pad8)") (class "Default")
      (node (ref "U10") (pin "8") (pinfunction "PB09_/_AIN[3]_/_SERCOM4/PAD1_8") (pintype "passive"))
    )
    (net (code "130") (name "unconnected-(U10A-PB10_{slash}_SERCOM4{slash}PAD2_{slash}_GCLK_IO[4]-Pad19)") (class "Default")
      (node (ref "U10") (pin "19") (pinfunction "PB10_/_SERCOM4/PAD2_/_GCLK_IO[4]_19") (pintype "passive"))
    )
    (net (code "131") (name "unconnected-(U10A-PB11_{slash}_SERCOM4{slash}PAD3_{slash}_GCLK_IO[5]-Pad20)") (class "Default")
      (node (ref "U10") (pin "20") (pinfunction "PB11_/_SERCOM4/PAD3_/_GCLK_IO[5]_20") (pintype "passive"))
    )
    (net (code "132") (name "unconnected-(U10A-PB22-Pad37)") (class "Default")
      (node (ref "U10") (pin "37") (pinfunction "PB22_37") (pintype "passive"))
    )
    (net (code "133") (name "unconnected-(U10A-PB23-Pad38)") (class "Default")
      (node (ref "U10") (pin "38") (pinfunction "PB23_38") (pintype "passive"))
    )
  )
)
